# untitled1.net
KiCad netlist of a schematic drawn in EAGLE
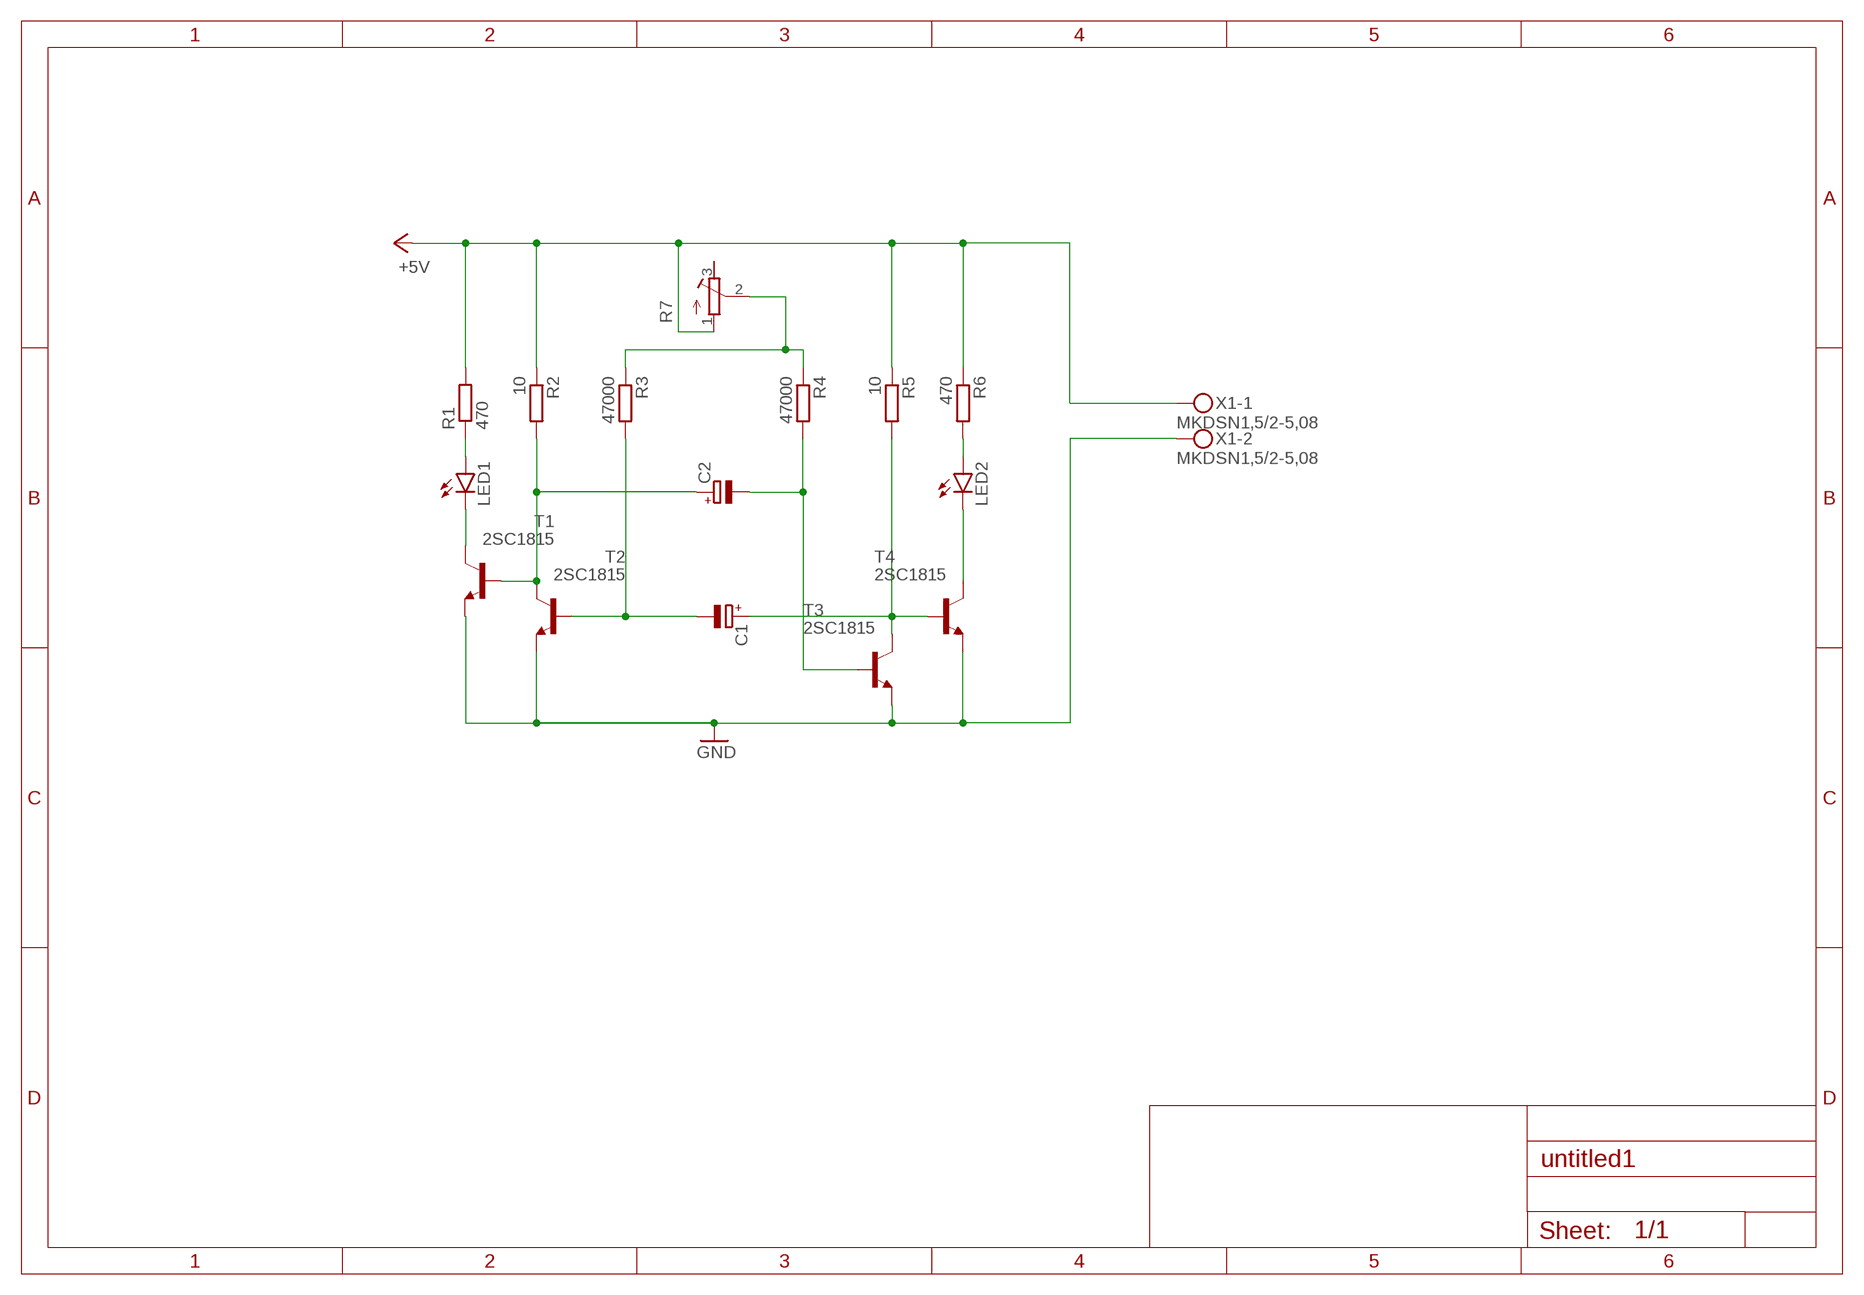
[diagram p0: schematic, sheet 1]

(export (version "E")
  (design (tool "Eeschema 10.0.6"))
  (components
    (comp (ref "C1")
      (value "CPOL-EUE3.5-8")
      (footprint "eagle-import:E3,5-8")
      (libsource (lib "eagle-import") (part "CPOL-EUE3.5-8"))
    )
    (comp (ref "C2")
      (value "CPOL-EUE3.5-8")
      (footprint "eagle-import:E3,5-8")
      (libsource (lib "eagle-import") (part "CPOL-EUE3.5-8"))
    )
    (comp (ref "LED1")
      (value "LED5MM")
      (footprint "eagle-import:LED5MM")
      (libsource (lib "eagle-import") (part "LED5MM"))
    )
    (comp (ref "LED2")
      (value "LED5MM")
      (footprint "eagle-import:LED5MM")
      (libsource (lib "eagle-import") (part "LED5MM"))
    )
    (comp (ref "R1")
      (value "470")
      (footprint "eagle-import:0309_12")
      (libsource (lib "eagle-import") (part "R-EU_0309/12"))
    )
    (comp (ref "R2")
      (value "10")
      (footprint "eagle-import:0309_12")
      (libsource (lib "eagle-import") (part "R-EU_0309/12"))
    )
    (comp (ref "R3")
      (value "47000")
      (footprint "eagle-import:0309_12")
      (libsource (lib "eagle-import") (part "R-EU_0309/12"))
    )
    (comp (ref "R4")
      (value "47000")
      (footprint "eagle-import:0309_12")
      (libsource (lib "eagle-import") (part "R-EU_0309/12"))
    )
    (comp (ref "R5")
      (value "10")
      (footprint "eagle-import:0309_12")
      (libsource (lib "eagle-import") (part "R-EU_0309/12"))
    )
    (comp (ref "R6")
      (value "470")
      (footprint "eagle-import:0309_12")
      (libsource (lib "eagle-import") (part "R-EU_0309/12"))
    )
    (comp (ref "R7")
      (value "R-TRIMM74X")
      (footprint "eagle-import:RTRIM74X")
      (libsource (lib "eagle-import") (part "R-TRIMM74X"))
    )
    (comp (ref "T1")
      (value "2SC1815")
      (footprint "eagle-import:TO92-ECB")
      (libsource (lib "eagle-import") (part "2SC1815"))
    )
    (comp (ref "T2")
      (value "2SC1815")
      (footprint "eagle-import:TO92-ECB")
      (libsource (lib "eagle-import") (part "2SC1815"))
    )
    (comp (ref "T3")
      (value "2SC1815")
      (footprint "eagle-import:TO92-ECB")
      (libsource (lib "eagle-import") (part "2SC1815"))
    )
    (comp (ref "T4")
      (value "2SC1815")
      (footprint "eagle-import:TO92-ECB")
      (libsource (lib "eagle-import") (part "2SC1815"))
    )
    (comp (ref "X1")
      (value "MKDSN1,5/2-5,08")
      (footprint "eagle-import:MKDSN1,5_2-5,08")
      (libsource (lib "eagle-import") (part "MKDSN1,5/2-5,08"))
    )
  )
  (nets
    (net (code "1") (name "+5V") (class "Default")
      (node (ref "R1") (pin "2") (pinfunction "2_2") (pintype "passive"))
      (node (ref "R2") (pin "1") (pinfunction "1_1") (pintype "passive"))
      (node (ref "R5") (pin "1") (pinfunction "1_1") (pintype "passive"))
      (node (ref "R6") (pin "1") (pinfunction "1_1") (pintype "passive"))
      (node (ref "R7") (pin "1") (pinfunction "A_1") (pintype "passive"))
      (node (ref "X1") (pin "1") (pinfunction "KL_1") (pintype "passive"))
    )
    (net (code "2") (name "GND") (class "Default")
      (node (ref "T1") (pin "E") (pinfunction "E_E") (pintype "passive"))
      (node (ref "T2") (pin "E") (pinfunction "E_E") (pintype "passive"))
      (node (ref "T3") (pin "E") (pinfunction "E_E") (pintype "passive"))
      (node (ref "T4") (pin "E") (pinfunction "E_E") (pintype "passive"))
      (node (ref "X1") (pin "2") (pinfunction "KL_2") (pintype "passive"))
    )
    (net (code "3") (name "Net-(C1-Pad+)") (class "Default")
      (node (ref "C1") (pin "+") (pinfunction "+_+") (pintype "passive"))
      (node (ref "R5") (pin "2") (pinfunction "2_2") (pintype "passive"))
      (node (ref "T3") (pin "C") (pinfunction "C_C") (pintype "passive"))
      (node (ref "T4") (pin "B") (pinfunction "B_B") (pintype "passive"))
    )
    (net (code "4") (name "Net-(C1-Pad-)") (class "Default")
      (node (ref "C1") (pin "-") (pinfunction "-_-") (pintype "passive"))
      (node (ref "R3") (pin "2") (pinfunction "2_2") (pintype "passive"))
      (node (ref "T2") (pin "B") (pinfunction "B_B") (pintype "passive"))
    )
    (net (code "5") (name "Net-(C2-Pad+)") (class "Default")
      (node (ref "C2") (pin "+") (pinfunction "+_+") (pintype "passive"))
      (node (ref "R2") (pin "2") (pinfunction "2_2") (pintype "passive"))
      (node (ref "T1") (pin "B") (pinfunction "B_B") (pintype "passive"))
      (node (ref "T2") (pin "C") (pinfunction "C_C") (pintype "passive"))
    )
    (net (code "6") (name "Net-(C2-Pad-)") (class "Default")
      (node (ref "C2") (pin "-") (pinfunction "-_-") (pintype "passive"))
      (node (ref "R4") (pin "2") (pinfunction "2_2") (pintype "passive"))
      (node (ref "T3") (pin "B") (pinfunction "B_B") (pintype "passive"))
    )
    (net (code "7") (name "Net-(LED1-C)") (class "Default")
      (node (ref "LED1") (pin "K") (pinfunction "C_K") (pintype "passive"))
      (node (ref "T1") (pin "C") (pinfunction "C_C") (pintype "passive"))
    )
    (net (code "8") (name "Net-(LED1-PadA)") (class "Default")
      (node (ref "LED1") (pin "A") (pinfunction "A_A") (pintype "passive"))
      (node (ref "R1") (pin "1") (pinfunction "1_1") (pintype "passive"))
    )
    (net (code "9") (name "Net-(LED2-C)") (class "Default")
      (node (ref "LED2") (pin "K") (pinfunction "C_K") (pintype "passive"))
      (node (ref "T4") (pin "C") (pinfunction "C_C") (pintype "passive"))
    )
    (net (code "10") (name "Net-(LED2-PadA)") (class "Default")
      (node (ref "LED2") (pin "A") (pinfunction "A_A") (pintype "passive"))
      (node (ref "R6") (pin "2") (pinfunction "2_2") (pintype "passive"))
    )
    (net (code "11") (name "Net-(R7-S)") (class "Default")
      (node (ref "R3") (pin "1") (pinfunction "1_1") (pintype "passive"))
      (node (ref "R4") (pin "1") (pinfunction "1_1") (pintype "passive"))
      (node (ref "R7") (pin "2") (pinfunction "S_2") (pintype "passive"))
    )
    (net (code "12") (name "unconnected-(R7-E-Pad3)") (class "Default")
      (node (ref "R7") (pin "3") (pinfunction "E_3") (pintype "passive"))
    )
  )
)
